# SparkFun_Main_Board_Double_v20.net
KiCad netlist of a schematic drawn in EAGLE
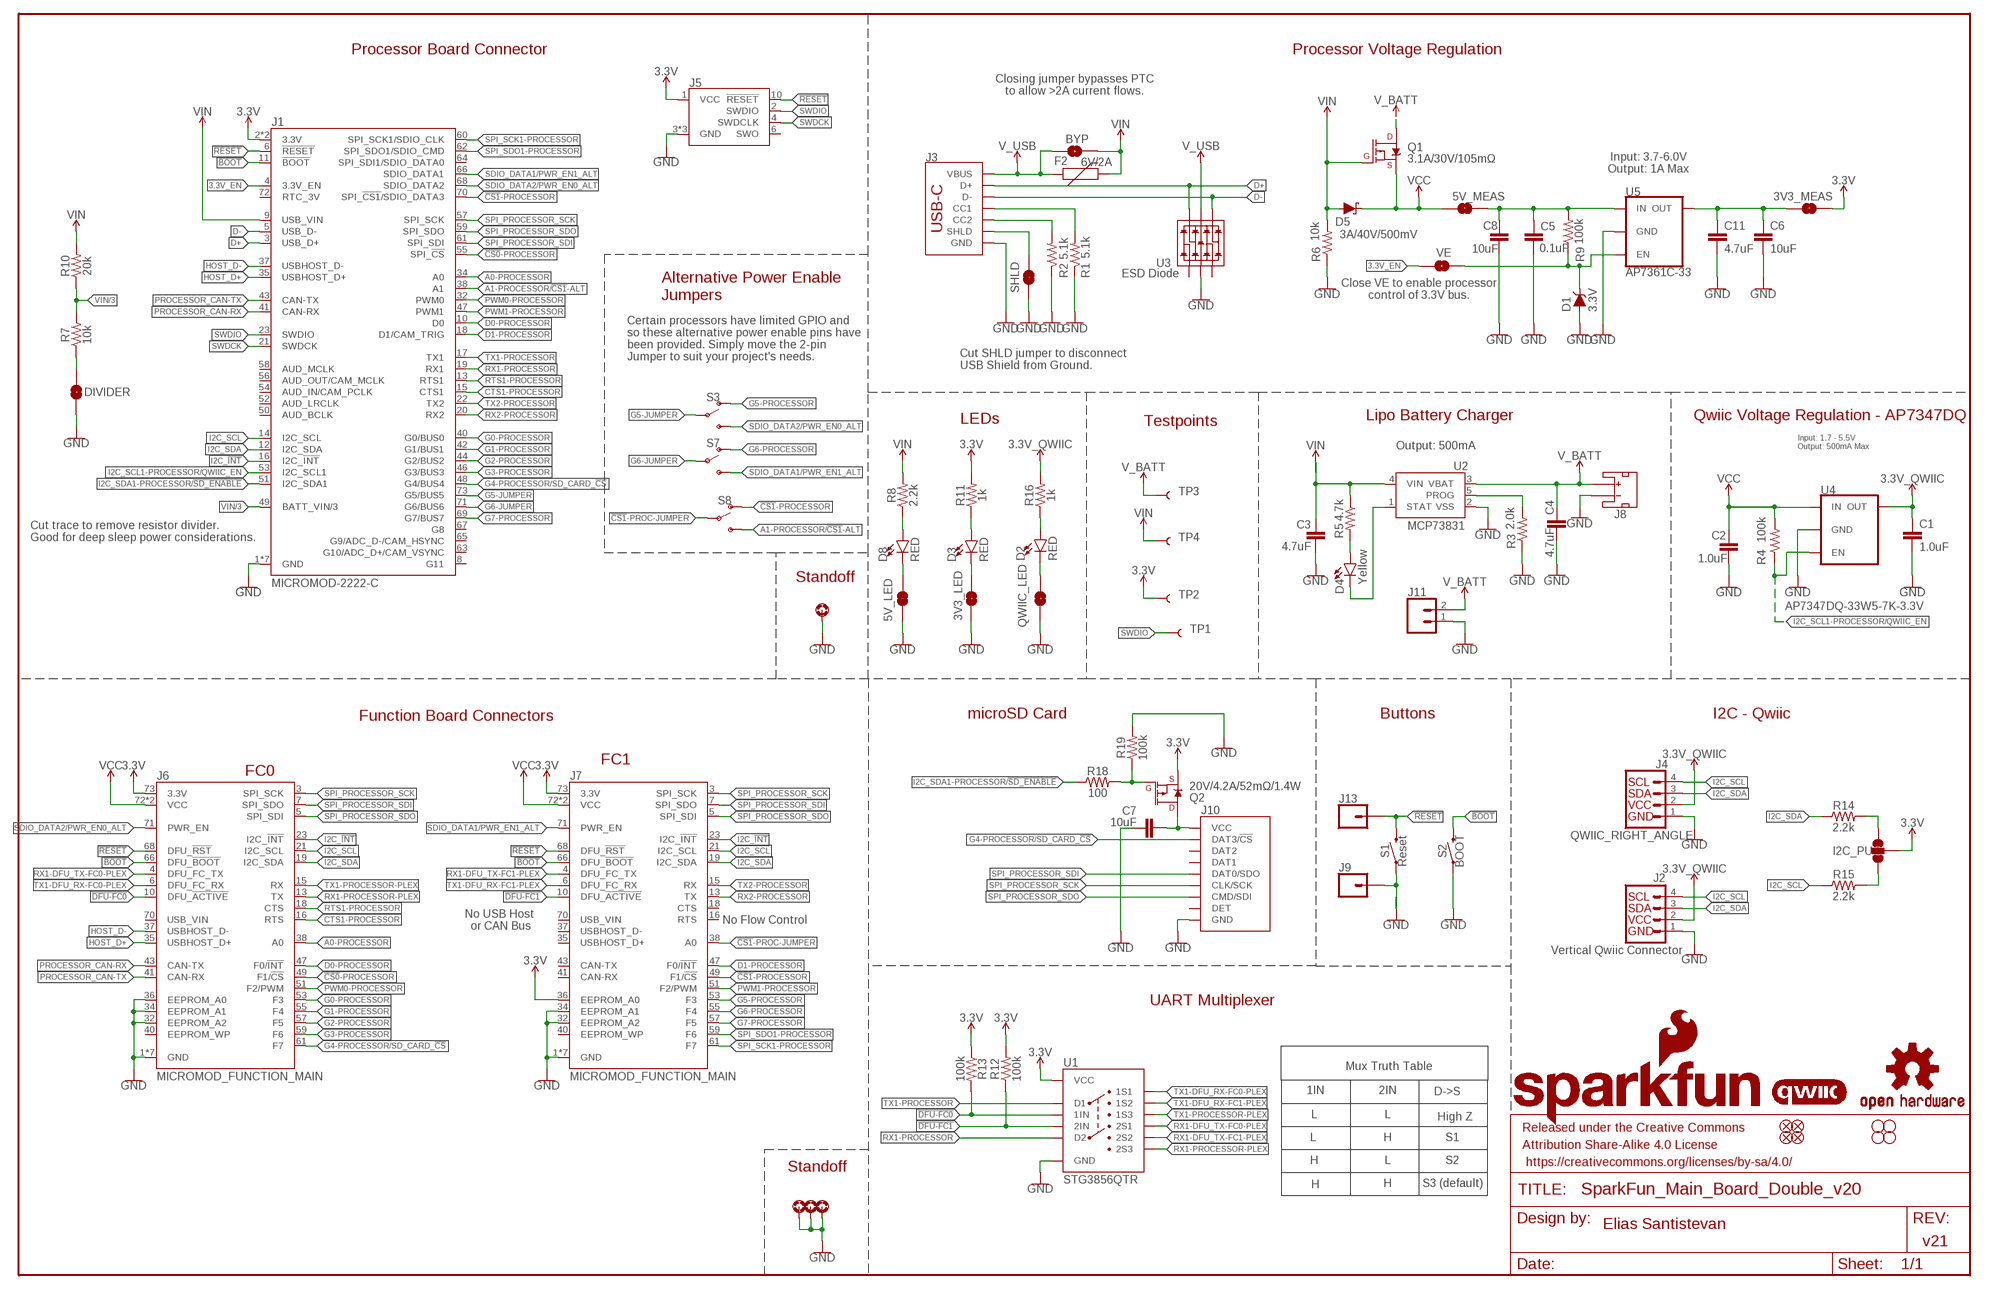
[diagram p0: schematic, sheet 1]

(export (version "E")
  (design (tool "Eeschema 10.0.6"))
  (components
    (comp (ref "3V3_LED")
      (value "JUMPER-SMT_2_NC_TRACE_SILK")
      (footprint "eagle-import:SMT-JUMPER_2_NC_TRACE_SILK")
      (libsource (lib "eagle-import") (part "JUMPER-SMT_2_NC_TRACE_SILK"))
    )
    (comp (ref "3V3_MEAS")
      (value "JUMPER-COMBO_2_NC_TRACE")
      (footprint "eagle-import:COMBO-JUMPER_2_NC_TRACE")
      (libsource (lib "eagle-import") (part "JUMPER-COMBO_2_NC_TRACE"))
    )
    (comp (ref "5V_LED")
      (value "JUMPER-SMT_2_NC_TRACE_SILK")
      (footprint "eagle-import:SMT-JUMPER_2_NC_TRACE_SILK")
      (libsource (lib "eagle-import") (part "JUMPER-SMT_2_NC_TRACE_SILK"))
    )
    (comp (ref "5V_MEAS")
      (value "JUMPER-COMBO_2_NC_TRACE")
      (footprint "eagle-import:COMBO-JUMPER_2_NC_TRACE")
      (libsource (lib "eagle-import") (part "JUMPER-COMBO_2_NC_TRACE"))
    )
    (comp (ref "BYP")
      (value "JUMPER-SMT_2_NO_SILK")
      (footprint "eagle-import:SMT-JUMPER_2_NO_SILK")
      (libsource (lib "eagle-import") (part "JUMPER-SMT_2_NO_SILK"))
    )
    (comp (ref "C1")
      (value "1.0uF")
      (footprint "eagle-import:0603")
      (libsource (lib "eagle-import") (part "1.0UF-0603-16V-10%"))
    )
    (comp (ref "C2")
      (value "1.0uF")
      (footprint "eagle-import:0603")
      (libsource (lib "eagle-import") (part "1.0UF-0603-16V-10%"))
    )
    (comp (ref "C3")
      (value "4.7uF")
      (footprint "eagle-import:0603")
      (libsource (lib "eagle-import") (part "4.7UF-0603-6.3V-(10%)"))
    )
    (comp (ref "C4")
      (value "4.7uF")
      (footprint "eagle-import:0603")
      (libsource (lib "eagle-import") (part "4.7UF-0603-35V-(20%)"))
    )
    (comp (ref "C5")
      (value "0.1uF")
      (footprint "eagle-import:0603")
      (libsource (lib "eagle-import") (part "0.1UF-0603-25V-(+80/-20%)"))
    )
    (comp (ref "C6")
      (value "10uF")
      (footprint "eagle-import:0805")
      (libsource (lib "eagle-import") (part "10UF-0805-10V-10%"))
    )
    (comp (ref "C7")
      (value "10uF")
      (footprint "eagle-import:0603")
      (libsource (lib "eagle-import") (part "10UF-0603-6.3V-20%"))
    )
    (comp (ref "C8")
      (value "10uF")
      (footprint "eagle-import:0805")
      (libsource (lib "eagle-import") (part "10UF-0805-10V-10%"))
    )
    (comp (ref "C11")
      (value "4.7uF")
      (footprint "eagle-import:0603")
      (libsource (lib "eagle-import") (part "4.7UF-0603-6.3V-(10%)"))
    )
    (comp (ref "D1")
      (value "3.3V")
      (footprint "eagle-import:SOD-323")
      (libsource (lib "eagle-import") (part "DIODE-ZENER-MM3Z3V3T1G"))
    )
    (comp (ref "D2")
      (value "RED")
      (footprint "eagle-import:LED-0603")
      (libsource (lib "eagle-import") (part "LED-RED0603"))
    )
    (comp (ref "D3")
      (value "RED")
      (footprint "eagle-import:LED-0603")
      (libsource (lib "eagle-import") (part "LED-RED0603"))
    )
    (comp (ref "D4")
      (value "Yellow")
      (footprint "eagle-import:LED-0603")
      (libsource (lib "eagle-import") (part "LED-YELLOW0603"))
    )
    (comp (ref "D5")
      (value "3A/40V/500mV")
      (footprint "eagle-import:SMA-DIODE")
      (libsource (lib "eagle-import") (part "DIODE-SCHOTTKY-B340A"))
    )
    (comp (ref "D8")
      (value "RED")
      (footprint "eagle-import:LED-0603")
      (libsource (lib "eagle-import") (part "LED-RED0603"))
    )
    (comp (ref "DIVIDER")
      (value "JUMPER-SMT_2_NC_TRACE_SILK")
      (footprint "eagle-import:SMT-JUMPER_2_NC_TRACE_SILK")
      (libsource (lib "eagle-import") (part "JUMPER-SMT_2_NC_TRACE_SILK"))
    )
    (comp (ref "F2")
      (value "6V/2A")
      (footprint "eagle-import:1210")
      (libsource (lib "eagle-import") (part "PPTC_6V2A"))
    )
    (comp (ref "FD1")
      (value "FIDUCIAL1X2")
      (footprint "eagle-import:FIDUCIAL-1X2")
      (libsource (lib "eagle-import") (part "FIDUCIAL1X2"))
    )
    (comp (ref "FD2")
      (value "FIDUCIAL1X2")
      (footprint "eagle-import:FIDUCIAL-1X2")
      (libsource (lib "eagle-import") (part "FIDUCIAL1X2"))
    )
    (comp (ref "FD3")
      (value "FIDUCIAL1X2")
      (footprint "eagle-import:FIDUCIAL-1X2")
      (libsource (lib "eagle-import") (part "FIDUCIAL1X2"))
    )
    (comp (ref "FD4")
      (value "FIDUCIAL1X2")
      (footprint "eagle-import:FIDUCIAL-1X2")
      (libsource (lib "eagle-import") (part "FIDUCIAL1X2"))
    )
    (comp (ref "FRAME1")
      (value "FRAME-LEDGER")
      (footprint "eagle-import:CREATIVE_COMMONS")
      (libsource (lib "eagle-import") (part "FRAME-LEDGER"))
    )
    (comp (ref "H2")
      (value "STAND-OFF-REFLOW-M2.5_2.5MM_TALL")
      (footprint "eagle-import:STAND-OFF-REFLOW-M2.5")
      (libsource (lib "eagle-import") (part "STAND-OFF-REFLOW-M2.5_2.5MM_TALL"))
    )
    (comp (ref "H3")
      (value "STAND-OFF-REFLOW-M2.5_2.5MM_TALL")
      (footprint "eagle-import:STAND-OFF-REFLOW-M2.5")
      (libsource (lib "eagle-import") (part "STAND-OFF-REFLOW-M2.5_2.5MM_TALL"))
    )
    (comp (ref "H4")
      (value "STAND-OFF-REFLOW-M2.5_2.5MM_TALL")
      (footprint "eagle-import:STAND-OFF-REFLOW-M2.5")
      (libsource (lib "eagle-import") (part "STAND-OFF-REFLOW-M2.5_2.5MM_TALL"))
    )
    (comp (ref "H8")
      (value "STAND-OFF-REFLOW-M2.5_2.5MM_TALL")
      (footprint "eagle-import:STAND-OFF-REFLOW-M2.5")
      (libsource (lib "eagle-import") (part "STAND-OFF-REFLOW-M2.5_2.5MM_TALL"))
    )
    (comp (ref "H14")
      (value "STAND-OFFTIGHT")
      (footprint "eagle-import:STAND-OFF-TIGHT")
      (libsource (lib "eagle-import") (part "STAND-OFFTIGHT"))
    )
    (comp (ref "H15")
      (value "STAND-OFFTIGHT")
      (footprint "eagle-import:STAND-OFF-TIGHT")
      (libsource (lib "eagle-import") (part "STAND-OFFTIGHT"))
    )
    (comp (ref "H16")
      (value "STAND-OFFTIGHT")
      (footprint "eagle-import:STAND-OFF-TIGHT")
      (libsource (lib "eagle-import") (part "STAND-OFFTIGHT"))
    )
    (comp (ref "H17")
      (value "STAND-OFFTIGHT")
      (footprint "eagle-import:STAND-OFF-TIGHT")
      (libsource (lib "eagle-import") (part "STAND-OFFTIGHT"))
    )
    (comp (ref "I2C_PU")
      (value "JUMPER-SMT_3_2-NC_TRACE_SILK")
      (footprint "eagle-import:SMT-JUMPER_3_2-NC_TRACE_SILK")
      (libsource (lib "eagle-import") (part "JUMPER-SMT_3_2-NC_TRACE_SILK"))
    )
    (comp (ref "J1")
      (value "MICROMOD-2222-C")
      (footprint "eagle-import:M.2-CONNECTOR-E")
      (libsource (lib "eagle-import") (part "MICROMOD-2222-C"))
    )
    (comp (ref "J2")
      (value "Vertical Qwiic Connector")
      (footprint "eagle-import:JST04_1MM_VERT")
      (libsource (lib "eagle-import") (part "QWIIC_CONNECTOR"))
    )
    (comp (ref "J3")
      (value "USB_C_2-LAYER_PADS")
      (footprint "eagle-import:USB-C-16P-2LAYER-PADS")
      (libsource (lib "eagle-import") (part "USB_C_2-LAYER_PADS"))
    )
    (comp (ref "J4")
      (value "QWIIC_RIGHT_ANGLE")
      (footprint "eagle-import:JST04_1MM_RA")
      (libsource (lib "eagle-import") (part "QWIIC_CONNECTORJS-1MM"))
    )
    (comp (ref "J5")
      (value "CORTEX_JTAG_DEBUG_MINIMUM_PTH")
      (footprint "eagle-import:2X5-PTH-1.27MM")
      (libsource (lib "eagle-import") (part "CORTEX_JTAG_DEBUG_MINIMUM_PTH"))
    )
    (comp (ref "J6")
      (value "MICROMOD_FUNCTION_MAIN")
      (footprint "eagle-import:M.2-CONNECTOR-E-FUNCTION-STANDARD")
      (libsource (lib "eagle-import") (part "MICROMOD_FUNCTION_MAIN"))
    )
    (comp (ref "J7")
      (value "MICROMOD_FUNCTION_MAIN")
      (footprint "eagle-import:M.2-CONNECTOR-E-FUNCTION-STANDARD")
      (libsource (lib "eagle-import") (part "MICROMOD_FUNCTION_MAIN"))
    )
    (comp (ref "J8")
      (value "JST_2MM_MALE")
      (footprint "eagle-import:JST-2-SMD")
      (libsource (lib "eagle-import") (part "JST_2MM_MALE"))
    )
    (comp (ref "J9")
      (value "CONN_01PTH_NO_SILK_YES_STOP")
      (footprint "eagle-import:1X01_NO_SILK")
      (libsource (lib "eagle-import") (part "CONN_01PTH_NO_SILK_YES_STOP"))
    )
    (comp (ref "J10")
      (value "MICRO-SD-PUSH-PUSH-EXT-PIN")
      (footprint "eagle-import:MICROSD-EXTERNALPIN")
      (libsource (lib "eagle-import") (part "MICRO-SD-PUSH-PUSH-EXT-PIN"))
    )
    (comp (ref "J11")
      (value "CONN_021X02_NO_SILK")
      (footprint "eagle-import:1X02_NO_SILK")
      (libsource (lib "eagle-import") (part "CONN_021X02_NO_SILK"))
    )
    (comp (ref "J13")
      (value "CONN_01PTH_NO_SILK_YES_STOP")
      (footprint "eagle-import:1X01_NO_SILK")
      (libsource (lib "eagle-import") (part "CONN_01PTH_NO_SILK_YES_STOP"))
    )
    (comp (ref "LOGO1")
      (value "QWIIC_LOGO_8MM")
      (footprint "eagle-import:QWIIC_8MM")
      (libsource (lib "eagle-import") (part "QWIIC_LOGO_8MM"))
    )
    (comp (ref "LOGO2")
      (value "SFE_LOGO_NAME_FLAME.3_INCH")
      (footprint "eagle-import:SFE_LOGO_NAME_FLAME_.3")
      (libsource (lib "eagle-import") (part "SFE_LOGO_NAME_FLAME.3_INCH"))
    )
    (comp (ref "LOGO3")
      (value "OSHW-LOGOL")
      (footprint "eagle-import:OSHW-LOGO-L")
      (libsource (lib "eagle-import") (part "OSHW-LOGOL"))
    )
    (comp (ref "Q1")
      (value "3.1A/30V/105mΩ")
      (footprint "eagle-import:SOT23-3")
      (libsource (lib "eagle-import") (part "MOSFET_PCH-DMG2307L"))
    )
    (comp (ref "Q2")
      (value "20V/4.2A/52mΩ/1.4W")
      (footprint "eagle-import:SOT23-3")
      (libsource (lib "eagle-import") (part "MOSFET_PCH-DMG2305UX-7"))
    )
    (comp (ref "QWIIC_LED")
      (value "JUMPER-SMT_2_NC_TRACE_SILK")
      (footprint "eagle-import:SMT-JUMPER_2_NC_TRACE_SILK")
      (libsource (lib "eagle-import") (part "JUMPER-SMT_2_NC_TRACE_SILK"))
    )
    (comp (ref "R1")
      (value "5.1k")
      (footprint "eagle-import:0603")
      (libsource (lib "eagle-import") (part "5.1KOHM5.1KOHM-0603-1/10W-1%"))
    )
    (comp (ref "R2")
      (value "5.1k")
      (footprint "eagle-import:0603")
      (libsource (lib "eagle-import") (part "5.1KOHM5.1KOHM-0603-1/10W-1%"))
    )
    (comp (ref "R3")
      (value "2.0k")
      (footprint "eagle-import:0603")
      (libsource (lib "eagle-import") (part "2.0KOHM-0603-1/10W-5%"))
    )
    (comp (ref "R4")
      (value "100k")
      (footprint "eagle-import:0603")
      (libsource (lib "eagle-import") (part "100KOHM-0603-1/10W-1%"))
    )
    (comp (ref "R5")
      (value "4.7k")
      (footprint "eagle-import:0603")
      (libsource (lib "eagle-import") (part "4.7KOHM-0603-1/10W-1%"))
    )
    (comp (ref "R6")
      (value "10k")
      (footprint "eagle-import:0603")
      (libsource (lib "eagle-import") (part "10KOHM-0603-1/10W-1%"))
    )
    (comp (ref "R7")
      (value "10k")
      (footprint "eagle-import:0603")
      (libsource (lib "eagle-import") (part "10KOHM-0603-1/10W-1%"))
    )
    (comp (ref "R8")
      (value "2.2k")
      (footprint "eagle-import:0603")
      (libsource (lib "eagle-import") (part "2.2KOHM-0603-1/10W-1%"))
    )
    (comp (ref "R9")
      (value "100k")
      (footprint "eagle-import:0603")
      (libsource (lib "eagle-import") (part "100KOHM-0603-1/10W-1%"))
    )
    (comp (ref "R10")
      (value "20k")
      (footprint "eagle-import:0603")
      (libsource (lib "eagle-import") (part "20KOHM-0603-1/10W-1%"))
    )
    (comp (ref "R11")
      (value "1k")
      (footprint "eagle-import:0603")
      (libsource (lib "eagle-import") (part "1KOHM-0603-1/10W-1%"))
    )
    (comp (ref "R12")
      (value "100k")
      (footprint "eagle-import:0603")
      (libsource (lib "eagle-import") (part "100KOHM-0603-1/10W-1%"))
    )
    (comp (ref "R13")
      (value "100k")
      (footprint "eagle-import:0603")
      (libsource (lib "eagle-import") (part "100KOHM-0603-1/10W-1%"))
    )
    (comp (ref "R14")
      (value "2.2k")
      (footprint "eagle-import:0603")
      (libsource (lib "eagle-import") (part "2.2KOHM-0603-1/10W-1%"))
    )
    (comp (ref "R15")
      (value "2.2k")
      (footprint "eagle-import:0603")
      (libsource (lib "eagle-import") (part "2.2KOHM-0603-1/10W-1%"))
    )
    (comp (ref "R16")
      (value "1k")
      (footprint "eagle-import:0603")
      (libsource (lib "eagle-import") (part "1KOHM-0603-1/10W-1%"))
    )
    (comp (ref "R18")
      (value "100")
      (footprint "eagle-import:0603")
      (libsource (lib "eagle-import") (part "100OHM-0603-1/10W-1%"))
    )
    (comp (ref "R19")
      (value "100k")
      (footprint "eagle-import:0603")
      (libsource (lib "eagle-import") (part "100KOHM-0603-1/10W-1%"))
    )
    (comp (ref "S1")
      (value "Reset")
      (footprint "eagle-import:TACTILE_SWITCH_SMD_5.2MM")
      (libsource (lib "eagle-import") (part "MOMENTARY-SWITCH-SPST-SMD-5.2-TALL-REDUNDANT"))
    )
    (comp (ref "S2")
      (value "BOOT")
      (footprint "eagle-import:TACTILE_SWITCH_SMD_5.2MM")
      (libsource (lib "eagle-import") (part "MOMENTARY-SWITCH-SPST-SMD-5.2-TALL-REDUNDANT"))
    )
    (comp (ref "S3")
      (value "SWITCH-SPDT-SMD-RIGHT-ANGLE")
      (footprint "eagle-import:SWITCH_SPST_SMD_A")
      (libsource (lib "eagle-import") (part "SWITCH-SPDT-SMD-RIGHT-ANGLE"))
    )
    (comp (ref "S7")
      (value "SWITCH-SPDT-SMD-RIGHT-ANGLE")
      (footprint "eagle-import:SWITCH_SPST_SMD_A")
      (libsource (lib "eagle-import") (part "SWITCH-SPDT-SMD-RIGHT-ANGLE"))
    )
    (comp (ref "S8")
      (value "SWITCH-SPDT-SMD-RIGHT-ANGLE")
      (footprint "eagle-import:SWITCH_SPST_SMD_A")
      (libsource (lib "eagle-import") (part "SWITCH-SPDT-SMD-RIGHT-ANGLE"))
    )
    (comp (ref "SHLD")
      (value "JUMPER-SMT_2_NC_TRACE_SILK")
      (footprint "eagle-import:SMT-JUMPER_2_NC_TRACE_SILK")
      (libsource (lib "eagle-import") (part "JUMPER-SMT_2_NC_TRACE_SILK"))
    )
    (comp (ref "TP1")
      (value "TEST-POINT3X5")
      (footprint "eagle-import:PAD.03X.05")
      (libsource (lib "eagle-import") (part "TEST-POINT3X5"))
    )
    (comp (ref "TP2")
      (value "TEST-POINT3X5")
      (footprint "eagle-import:PAD.03X.05")
      (libsource (lib "eagle-import") (part "TEST-POINT3X5"))
    )
    (comp (ref "TP3")
      (value "TEST-POINT3X5")
      (footprint "eagle-import:PAD.03X.05")
      (libsource (lib "eagle-import") (part "TEST-POINT3X5"))
    )
    (comp (ref "TP4")
      (value "TEST-POINT3X5")
      (footprint "eagle-import:PAD.03X.05")
      (libsource (lib "eagle-import") (part "TEST-POINT3X5"))
    )
    (comp (ref "U1")
      (value "STG3856QTR")
      (footprint "eagle-import:STG3856")
      (libsource (lib "eagle-import") (part "STG3856QTR"))
    )
    (comp (ref "U2")
      (value "MCP73831")
      (footprint "eagle-import:SOT23-5")
      (libsource (lib "eagle-import") (part "MCP73831"))
    )
    (comp (ref "U3")
      (value "ESD Diode")
      (footprint "eagle-import:SOT-23-6")
      (libsource (lib "eagle-import") (part "TVS_DIODE_ARRAYSMD"))
    )
    (comp (ref "U4")
      (value "AP7347DQ-33W5-7K-3.3V")
      (footprint "eagle-import:SOT25")
      (libsource (lib "eagle-import") (part "AP7347DQ-33W5-7K-3.3V"))
    )
    (comp (ref "U5")
      (value "AP7361C-33")
      (footprint "eagle-import:UDFN-8")
      (libsource (lib "eagle-import") (part "AP7361C-33FGEUDFN-8"))
    )
    (comp (ref "VE")
      (value "JUMPER-SMT_2_NO_SILK")
      (footprint "eagle-import:SMT-JUMPER_2_NO_SILK")
      (libsource (lib "eagle-import") (part "JUMPER-SMT_2_NO_SILK"))
    )
  )
  (nets
    (net (code "1") (name "/A1-PROCESSOR{slash}~{CS1}-ALT") (class "Default")
      (node (ref "J1") (pin "38") (pinfunction "A1_38") (pintype "bidirectional"))
      (node (ref "S8") (pin "3") (pinfunction "S_3") (pintype "passive"))
    )
    (net (code "2") (name "/G4-PROCESSOR{slash}SD_CARD_~{CS}") (class "Default")
      (node (ref "J1") (pin "48") (pinfunction "G4/BUS4_48") (pintype "bidirectional"))
      (node (ref "J10") (pin "2") (pinfunction "DAT3/~{CS}_2") (pintype "bidirectional"))
      (node (ref "J6") (pin "61") (pinfunction "F7_61") (pintype "bidirectional"))
    )
    (net (code "3") (name "/I2C_SDA1-PROCESSOR{slash}~{SD_ENABLE}") (class "Default")
      (node (ref "J1") (pin "51") (pinfunction "I2C_SDA1_51") (pintype "bidirectional"))
      (node (ref "R18") (pin "1") (pinfunction "1_1") (pintype "passive"))
    )
    (net (code "4") (name "/I2C_~{INT}") (class "Default")
      (node (ref "J1") (pin "16") (pinfunction "I2C_~{INT}_16") (pintype "bidirectional"))
      (node (ref "J6") (pin "23") (pinfunction "I2C_~{INT}_23") (pintype "bidirectional"))
      (node (ref "J7") (pin "23") (pinfunction "I2C_~{INT}_23") (pintype "bidirectional"))
    )
    (net (code "5") (name "/~{BOOT}") (class "Default")
      (node (ref "J1") (pin "11") (pinfunction "~{BOOT}_11") (pintype "bidirectional"))
      (node (ref "J6") (pin "66") (pinfunction "DFU_~{BOOT}_66") (pintype "bidirectional"))
      (node (ref "J7") (pin "66") (pinfunction "DFU_~{BOOT}_66") (pintype "bidirectional"))
      (node (ref "S2") (pin "3") (pinfunction "2_3") (pintype "passive"))
      (node (ref "S2") (pin "4") (pinfunction "2_4") (pintype "passive"))
    )
    (net (code "6") (name "/~{CS0}-PROCESSOR") (class "Default")
      (node (ref "J1") (pin "55") (pinfunction "SPI_~{CS}_55") (pintype "bidirectional"))
      (node (ref "J6") (pin "49") (pinfunction "F1/~{CS}_49") (pintype "bidirectional"))
    )
    (net (code "7") (name "/~{CS1}-PROC-JUMPER") (class "Default")
      (node (ref "J7") (pin "38") (pinfunction "A0_38") (pintype "bidirectional"))
      (node (ref "S8") (pin "2") (pinfunction "P_2") (pintype "passive"))
    )
    (net (code "8") (name "/~{CS1}-PROCESSOR") (class "Default")
      (node (ref "J1") (pin "70") (pinfunction "SPI_~{CS1}/SDIO_DATA3_70") (pintype "bidirectional"))
      (node (ref "J7") (pin "49") (pinfunction "F1/~{CS}_49") (pintype "bidirectional"))
      (node (ref "S8") (pin "1") (pinfunction "O_1") (pintype "passive"))
    )
    (net (code "9") (name "/~{DFU-FC0}") (class "Default")
      (node (ref "J6") (pin "10") (pinfunction "DFU_~{ACTIVE}_10") (pintype "bidirectional"))
      (node (ref "R13") (pin "2") (pinfunction "2_2") (pintype "passive"))
      (node (ref "U1") (pin "P12") (pinfunction "1IN_P12") (pintype "bidirectional"))
    )
    (net (code "10") (name "/~{DFU-FC1}") (class "Default")
      (node (ref "J7") (pin "10") (pinfunction "DFU_~{ACTIVE}_10") (pintype "bidirectional"))
      (node (ref "R12") (pin "1") (pinfunction "1_1") (pintype "passive"))
      (node (ref "U1") (pin "P10") (pinfunction "2IN_P10") (pintype "bidirectional"))
    )
    (net (code "11") (name "/~{RESET}") (class "Default")
      (node (ref "J1") (pin "6") (pinfunction "~{RESET}_6") (pintype "bidirectional"))
      (node (ref "J13") (pin "1") (pinfunction "1_1") (pintype "passive"))
      (node (ref "J5") (pin "10") (pinfunction "~{RESET}_10") (pintype "bidirectional"))
      (node (ref "J6") (pin "68") (pinfunction "DFU_~{RST}_68") (pintype "bidirectional"))
      (node (ref "J7") (pin "68") (pinfunction "DFU_~{RST}_68") (pintype "bidirectional"))
      (node (ref "S1") (pin "3") (pinfunction "2_3") (pintype "passive"))
      (node (ref "S1") (pin "4") (pinfunction "2_4") (pintype "passive"))
    )
    (net (code "12") (name "3.3V") (class "Default")
      (node (ref "3V3_MEAS") (pin "2") (pinfunction "2_2") (pintype "passive"))
      (node (ref "3V3_MEAS") (pin "4") (pinfunction "2_4") (pintype "passive"))
      (node (ref "I2C_PU") (pin "2") (pinfunction "2_2") (pintype "passive"))
      (node (ref "J1") (pin "2") (pinfunction "3.3V_2") (pintype "bidirectional"))
      (node (ref "J1") (pin "74") (pinfunction "3.3V_74") (pintype "bidirectional"))
      (node (ref "J5") (pin "1") (pinfunction "VCC_1") (pintype "bidirectional"))
      (node (ref "J6") (pin "73") (pinfunction "3.3V_73") (pintype "bidirectional"))
      (node (ref "J7") (pin "36") (pinfunction "EEPROM_A0_36") (pintype "bidirectional"))
      (node (ref "J7") (pin "73") (pinfunction "3.3V_73") (pintype "bidirectional"))
      (node (ref "Q2") (pin "2") (pinfunction "S_2") (pintype "bidirectional"))
      (node (ref "R11") (pin "2") (pinfunction "2_2") (pintype "passive"))
      (node (ref "R12") (pin "2") (pinfunction "2_2") (pintype "passive"))
      (node (ref "R13") (pin "1") (pinfunction "1_1") (pintype "passive"))
      (node (ref "TP2") (pin "1") (pinfunction "1_1") (pintype "bidirectional"))
      (node (ref "U1") (pin "P11") (pinfunction "VCC_P11") (pintype "power_in"))
    )
    (net (code "13") (name "3.3V_EN") (class "Default")
      (node (ref "J1") (pin "4") (pinfunction "3.3V_EN_4") (pintype "bidirectional"))
      (node (ref "VE") (pin "1") (pinfunction "1_1") (pintype "passive"))
    )
    (net (code "14") (name "3.3V_QWIIC") (class "Default")
      (node (ref "C1") (pin "1") (pinfunction "1_1") (pintype "passive"))
      (node (ref "J2") (pin "2") (pinfunction "2_2") (pintype "power_in"))
      (node (ref "J4") (pin "2") (pinfunction "2_2") (pintype "power_in"))
      (node (ref "R16") (pin "2") (pinfunction "2_2") (pintype "passive"))
      (node (ref "U4") (pin "5") (pinfunction "OUT_5") (pintype "passive"))
    )
    (net (code "15") (name "A0-PROCESSOR") (class "Default")
      (node (ref "J1") (pin "34") (pinfunction "A0_34") (pintype "bidirectional"))
      (node (ref "J6") (pin "38") (pinfunction "A0_38") (pintype "bidirectional"))
    )
    (net (code "16") (name "CTS1-PROCESSOR") (class "Default")
      (node (ref "J1") (pin "15") (pinfunction "CTS1_15") (pintype "bidirectional"))
      (node (ref "J6") (pin "16") (pinfunction "RTS_16") (pintype "bidirectional"))
    )
    (net (code "17") (name "D+") (class "Default")
      (node (ref "J1") (pin "3") (pinfunction "USB_D+_3") (pintype "bidirectional"))
      (node (ref "J3") (pin "A6") (pinfunction "D+_A6") (pintype "bidirectional"))
      (node (ref "J3") (pin "B6") (pinfunction "D+_B6") (pintype "bidirectional"))
      (node (ref "U3") (pin "6") (pinfunction "IO4_6") (pintype "bidirectional"))
    )
    (net (code "18") (name "D-") (class "Default")
      (node (ref "J1") (pin "5") (pinfunction "USB_D-_5") (pintype "bidirectional"))
      (node (ref "J3") (pin "A7") (pinfunction "D-_A7") (pintype "bidirectional"))
      (node (ref "J3") (pin "B7") (pinfunction "D-_B7") (pintype "bidirectional"))
      (node (ref "U3") (pin "4") (pinfunction "IO3_4") (pintype "bidirectional"))
    )
    (net (code "19") (name "D0-PROCESSOR") (class "Default")
      (node (ref "J1") (pin "10") (pinfunction "D0_10") (pintype "bidirectional"))
      (node (ref "J6") (pin "47") (pinfunction "F0/~{INT}_47") (pintype "bidirectional"))
    )
    (net (code "20") (name "D1-PROCESSOR") (class "Default")
      (node (ref "J1") (pin "18") (pinfunction "D1/CAM_TRIG_18") (pintype "bidirectional"))
      (node (ref "J7") (pin "47") (pinfunction "F0/~{INT}_47") (pintype "bidirectional"))
    )
    (net (code "21") (name "G0-PROCESSOR") (class "Default")
      (node (ref "J1") (pin "40") (pinfunction "G0/BUS0_40") (pintype "bidirectional"))
      (node (ref "J6") (pin "53") (pinfunction "F3_53") (pintype "bidirectional"))
    )
    (net (code "22") (name "G1-PROCESSOR") (class "Default")
      (node (ref "J1") (pin "42") (pinfunction "G1/BUS1_42") (pintype "bidirectional"))
      (node (ref "J6") (pin "55") (pinfunction "F4_55") (pintype "bidirectional"))
    )
    (net (code "23") (name "G2-PROCESSOR") (class "Default")
      (node (ref "J1") (pin "44") (pinfunction "G2/BUS2_44") (pintype "bidirectional"))
      (node (ref "J6") (pin "57") (pinfunction "F5_57") (pintype "bidirectional"))
    )
    (net (code "24") (name "G3-PROCESSOR") (class "Default")
      (node (ref "J1") (pin "46") (pinfunction "G3/BUS3_46") (pintype "bidirectional"))
      (node (ref "J6") (pin "59") (pinfunction "F6_59") (pintype "bidirectional"))
    )
    (net (code "25") (name "G5-JUMPER") (class "Default")
      (node (ref "J1") (pin "73") (pinfunction "G5/BUS5_73") (pintype "bidirectional"))
      (node (ref "S3") (pin "2") (pinfunction "P_2") (pintype "passive"))
    )
    (net (code "26") (name "G5-PROCESSOR") (class "Default")
      (node (ref "J7") (pin "53") (pinfunction "F3_53") (pintype "bidirectional"))
      (node (ref "S3") (pin "1") (pinfunction "O_1") (pintype "passive"))
    )
    (net (code "27") (name "G6-JUMPER") (class "Default")
      (node (ref "J1") (pin "71") (pinfunction "G6/BUS6_71") (pintype "bidirectional"))
      (node (ref "S7") (pin "2") (pinfunction "P_2") (pintype "passive"))
    )
    (net (code "28") (name "G6-PROCESSOR") (class "Default")
      (node (ref "J7") (pin "55") (pinfunction "F4_55") (pintype "bidirectional"))
      (node (ref "S7") (pin "1") (pinfunction "O_1") (pintype "passive"))
    )
    (net (code "29") (name "G7-PROCESSOR") (class "Default")
      (node (ref "J1") (pin "69") (pinfunction "G7/BUS7_69") (pintype "bidirectional"))
      (node (ref "J7") (pin "57") (pinfunction "F5_57") (pintype "bidirectional"))
    )
    (net (code "30") (name "GND") (class "Default")
      (node (ref "3V3_LED") (pin "1") (pinfunction "1_1") (pintype "passive"))
      (node (ref "5V_LED") (pin "1") (pinfunction "1_1") (pintype "passive"))
      (node (ref "C1") (pin "2") (pinfunction "2_2") (pintype "passive"))
      (node (ref "C11") (pin "2") (pinfunction "2_2") (pintype "passive"))
      (node (ref "C2") (pin "2") (pinfunction "2_2") (pintype "passive"))
      (node (ref "C3") (pin "2") (pinfunction "2_2") (pintype "passive"))
      (node (ref "C4") (pin "2") (pinfunction "2_2") (pintype "passive"))
      (node (ref "C5") (pin "2") (pinfunction "2_2") (pintype "passive"))
      (node (ref "C6") (pin "2") (pinfunction "2_2") (pintype "passive"))
      (node (ref "C7") (pin "1") (pinfunction "1_1") (pintype "passive"))
      (node (ref "C8") (pin "2") (pinfunction "2_2") (pintype "passive"))
      (node (ref "D1") (pin "A") (pinfunction "A_A") (pintype "passive"))
      (node (ref "DIVIDER") (pin "1") (pinfunction "1_1") (pintype "passive"))
      (node (ref "H2") (pin "1") (pinfunction "1_1") (pintype "bidirectional"))
      (node (ref "H3") (pin "1") (pinfunction "1_1") (pintype "bidirectional"))
      (node (ref "H4") (pin "1") (pinfunction "1_1") (pintype "bidirectional"))
      (node (ref "H8") (pin "1") (pinfunction "1_1") (pintype "bidirectional"))
      (node (ref "J1") (pin "1") (pinfunction "GND_1") (pintype "bidirectional"))
      (node (ref "J1") (pin "33") (pinfunction "GND_33") (pintype "bidirectional"))
      (node (ref "J1") (pin "36") (pinfunction "GND_36") (pintype "bidirectional"))
      (node (ref "J1") (pin "39") (pinfunction "GND_39") (pintype "bidirectional"))
      (node (ref "J1") (pin "45") (pinfunction "GND_45") (pintype "bidirectional"))
      (node (ref "J1") (pin "7") (pinfunction "GND_7") (pintype "bidirectional"))
      (node (ref "J1") (pin "75") (pinfunction "GND_75") (pintype "bidirectional"))
      (node (ref "J10") (pin "10") (pinfunction "GND_10") (pintype "bidirectional"))
      (node (ref "J10") (pin "11") (pinfunction "GND_11") (pintype "bidirectional"))
      (node (ref "J10") (pin "12") (pinfunction "GND_12") (pintype "bidirectional"))
      (node (ref "J10") (pin "13") (pinfunction "GND_13") (pintype "bidirectional"))
      (node (ref "J10") (pin "6") (pinfunction "GND_6") (pintype "bidirectional"))
      (node (ref "J11") (pin "1") (pinfunction "1_1") (pintype "passive"))
      (node (ref "J2") (pin "1") (pinfunction "1_1") (pintype "power_in"))
      (node (ref "J3") (pin "GND") (pinfunction "GND_GND") (pintype "bidirectional"))
      (node (ref "J3") (pin "GND2") (pinfunction "GND_GND2") (pintype "bidirectional"))
      (node (ref "J4") (pin "1") (pinfunction "1_1") (pintype "power_in"))
      (node (ref "J5") (pin "3") (pinfunction "GND_3") (pintype "bidirectional"))
      (node (ref "J5") (pin "5") (pinfunction "GND_5") (pintype "bidirectional"))
      (node (ref "J5") (pin "9") (pinfunction "GND_9") (pintype "bidirectional"))
      (node (ref "J6") (pin "1") (pinfunction "GND_1") (pintype "bidirectional"))
      (node (ref "J6") (pin "2") (pinfunction "GND_2") (pintype "bidirectional"))
      (node (ref "J6") (pin "32") (pinfunction "EEPROM_A2_32") (pintype "bidirectional"))
      (node (ref "J6") (pin "33") (pinfunction "GND_33") (pintype "bidirectional"))
      (node (ref "J6") (pin "34") (pinfunction "EEPROM_A1_34") (pintype "bidirectional"))
      (node (ref "J6") (pin "36") (pinfunction "EEPROM_A0_36") (pintype "bidirectional"))
      (node (ref "J6") (pin "39") (pinfunction "GND_39") (pintype "bidirectional"))
      (node (ref "J6") (pin "45") (pinfunction "GND_45") (pintype "bidirectional"))
      (node (ref "J6") (pin "75") (pinfunction "GND_75") (pintype "bidirectional"))
      (node (ref "J6") (pin "8") (pinfunction "GND_8") (pintype "bidirectional"))
      (node (ref "J7") (pin "1") (pinfunction "GND_1") (pintype "bidirectional"))
      (node (ref "J7") (pin "2") (pinfunction "GND_2") (pintype "bidirectional"))
      (node (ref "J7") (pin "32") (pinfunction "EEPROM_A2_32") (pintype "bidirectional"))
      (node (ref "J7") (pin "33") (pinfunction "GND_33") (pintype "bidirectional"))
      (node (ref "J7") (pin "34") (pinfunction "EEPROM_A1_34") (pintype "bidirectional"))
      (node (ref "J7") (pin "39") (pinfunction "GND_39") (pintype "bidirectional"))
      (node (ref "J7") (pin "45") (pinfunction "GND_45") (pintype "bidirectional"))
      (node (ref "J7") (pin "75") (pinfunction "GND_75") (pintype "bidirectional"))
      (node (ref "J7") (pin "8") (pinfunction "GND_8") (pintype "bidirectional"))
      (node (ref "J8") (pin "1") (pinfunction "-_1") (pintype "bidirectional"))
      (node (ref "J9") (pin "1") (pinfunction "1_1") (pintype "passive"))
      (node (ref "QWIIC_LED") (pin "1") (pinfunction "1_1") (pintype "passive"))
      (node (ref "R1") (pin "1") (pinfunction "1_1") (pintype "passive"))
      (node (ref "R19") (pin "2") (pinfunction "2_2") (pintype "passive"))
      (node (ref "R2") (pin "1") (pinfunction "1_1") (pintype "passive"))
      (node (ref "R3") (pin "1") (pinfunction "1_1") (pintype "passive"))
      (node (ref "R6") (pin "1") (pinfunction "1_1") (pintype "passive"))
      (node (ref "S1") (pin "1") (pinfunction "1_1") (pintype "passive"))
      (node (ref "S1") (pin "2") (pinfunction "1_2") (pintype "passive"))
      (node (ref "S2") (pin "1") (pinfunction "1_1") (pintype "passive"))
      (node (ref "S2") (pin "2") (pinfunction "1_2") (pintype "passive"))
      (node (ref "SHLD") (pin "1") (pinfunction "1_1") (pintype "passive"))
      (node (ref "U1") (pin "P5") (pinfunction "GND_P5") (pintype "power_in"))
      (node (ref "U2") (pin "2") (pinfunction "VSS_2") (pintype "power_in"))
      (node (ref "U3") (pin "2") (pinfunction "VSS_2") (pintype "bidirectional"))
      (node (ref "U4") (pin "2") (pinfunction "GND_2") (pintype "input"))
      (node (ref "U5") (pin "4") (pinfunction "GND_4") (pintype "input"))
      (node (ref "U5") (pin "EP") (pinfunction "GND_EP") (pintype "input"))
    )
    (net (code "31") (name "HOST_D+") (class "Default")
      (node (ref "J1") (pin "35") (pinfunction "USBHOST_D+_35") (pintype "bidirectional"))
      (node (ref "J6") (pin "35") (pinfunction "USBHOST_D+_35") (pintype "bidirectional"))
    )
    (net (code "32") (name "HOST_D-") (class "Default")
      (node (ref "J1") (pin "37") (pinfunction "USBHOST_D-_37") (pintype "bidirectional"))
      (node (ref "J6") (pin "37") (pinfunction "USBHOST_D-_37") (pintype "bidirectional"))
    )
    (net (code "33") (name "I2C_SCL") (class "Default")
      (node (ref "J1") (pin "14") (pinfunction "I2C_SCL_14") (pintype "bidirectional"))
      (node (ref "J2") (pin "4") (pinfunction "4_4") (pintype "passive"))
      (node (ref "J4") (pin "4") (pinfunction "4_4") (pintype "passive"))
      (node (ref "J6") (pin "21") (pinfunction "I2C_SCL_21") (pintype "bidirectional"))
      (node (ref "J7") (pin "21") (pinfunction "I2C_SCL_21") (pintype "bidirectional"))
      (node (ref "R15") (pin "1") (pinfunction "1_1") (pintype "passive"))
    )
    (net (code "34") (name "I2C_SCL1-PROCESSOR{slash}QWIIC_EN") (class "Default")
      (node (ref "J1") (pin "53") (pinfunction "I2C_SCL1_53") (pintype "bidirectional"))
      (node (ref "R4") (pin "1") (pinfunction "1_1") (pintype "passive"))
      (node (ref "U4") (pin "3") (pinfunction "EN_3") (pintype "input"))
    )
    (net (code "35") (name "I2C_SDA") (class "Default")
      (node (ref "J1") (pin "12") (pinfunction "I2C_SDA_12") (pintype "bidirectional"))
      (node (ref "J2") (pin "3") (pinfunction "3_3") (pintype "passive"))
      (node (ref "J4") (pin "3") (pinfunction "3_3") (pintype "passive"))
      (node (ref "J6") (pin "19") (pinfunction "I2C_SDA_19") (pintype "bidirectional"))
      (node (ref "J7") (pin "19") (pinfunction "I2C_SDA_19") (pintype "bidirectional"))
      (node (ref "R14") (pin "1") (pinfunction "1_1") (pintype "passive"))
    )
    (net (code "36") (name "Net-(3V3_LED-Pad2)") (class "Default")
      (node (ref "3V3_LED") (pin "2") (pinfunction "2_2") (pintype "passive"))
      (node (ref "D3") (pin "C") (pinfunction "C_C") (pintype "passive"))
    )
    (net (code "37") (name "Net-(5V_LED-Pad2)") (class "Default")
      (node (ref "5V_LED") (pin "2") (pinfunction "2_2") (pintype "passive"))
      (node (ref "D8") (pin "C") (pinfunction "C_C") (pintype "passive"))
    )
    (net (code "38") (name "Net-(D2-PadA)") (class "Default")
      (node (ref "D2") (pin "A") (pinfunction "A_A") (pintype "passive"))
      (node (ref "R16") (pin "1") (pinfunction "1_1") (pintype "passive"))
    )
    (net (code "39") (name "Net-(D2-PadC)") (class "Default")
      (node (ref "D2") (pin "C") (pinfunction "C_C") (pintype "passive"))
      (node (ref "QWIIC_LED") (pin "2") (pinfunction "2_2") (pintype "passive"))
    )
    (net (code "40") (name "Net-(D3-PadA)") (class "Default")
      (node (ref "D3") (pin "A") (pinfunction "A_A") (pintype "passive"))
      (node (ref "R11") (pin "1") (pinfunction "1_1") (pintype "passive"))
    )
    (net (code "41") (name "Net-(D4-PadA)") (class "Default")
      (node (ref "D4") (pin "A") (pinfunction "A_A") (pintype "passive"))
      (node (ref "R5") (pin "2") (pinfunction "2_2") (pintype "passive"))
    )
    (net (code "42") (name "Net-(D8-PadA)") (class "Default")
      (node (ref "D8") (pin "A") (pinfunction "A_A") (pintype "passive"))
      (node (ref "R8") (pin "1") (pinfunction "1_1") (pintype "passive"))
    )
    (net (code "43") (name "Net-(DIVIDER-Pad2)") (class "Default")
      (node (ref "DIVIDER") (pin "2") (pinfunction "2_2") (pintype "passive"))
      (node (ref "R7") (pin "1") (pinfunction "1_1") (pintype "passive"))
    )
    (net (code "44") (name "Net-(I2C_PU-Pad1)") (class "Default")
      (node (ref "I2C_PU") (pin "1") (pinfunction "1_1") (pintype "passive"))
      (node (ref "R15") (pin "2") (pinfunction "2_2") (pintype "passive"))
    )
    (net (code "45") (name "Net-(I2C_PU-Pad3)") (class "Default")
      (node (ref "I2C_PU") (pin "3") (pinfunction "3_3") (pintype "passive"))
      (node (ref "R14") (pin "2") (pinfunction "2_2") (pintype "passive"))
    )
    (net (code "46") (name "Net-(J3-CC1)") (class "Default")
      (node (ref "J3") (pin "A5") (pinfunction "CC1_A5") (pintype "bidirectional"))
      (node (ref "R1") (pin "2") (pinfunction "2_2") (pintype "passive"))
    )
    (net (code "47") (name "Net-(J3-CC2)") (class "Default")
      (node (ref "J3") (pin "B5") (pinfunction "CC2_B5") (pintype "bidirectional"))
      (node (ref "R2") (pin "2") (pinfunction "2_2") (pintype "passive"))
    )
    (net (code "48") (name "Net-(J3-SHLD-PadSHLD1)") (class "Default")
      (node (ref "J3") (pin "SHLD1") (pinfunction "SHLD_SHLD1") (pintype "bidirectional"))
      (node (ref "J3") (pin "SHLD2") (pinfunction "SHLD_SHLD2") (pintype "bidirectional"))
      (node (ref "J3") (pin "SHLD3") (pinfunction "SHLD_SHLD3") (pintype "bidirectional"))
      (node (ref "J3") (pin "SHLD4") (pinfunction "SHLD_SHLD4") (pintype "bidirectional"))
      (node (ref "SHLD") (pin "2") (pinfunction "2_2") (pintype "passive"))
    )
    (net (code "49") (name "Net-(J10-VCC)") (class "Default")
      (node (ref "C7") (pin "2") (pinfunction "2_2") (pintype "passive"))
      (node (ref "J10") (pin "4") (pinfunction "VCC_4") (pintype "bidirectional"))
      (node (ref "Q2") (pin "3") (pinfunction "D_3") (pintype "bidirectional"))
    )
    (net (code "50") (name "Net-(Q2-G)") (class "Default")
      (node (ref "Q2") (pin "1") (pinfunction "G_1") (pintype "bidirectional"))
      (node (ref "R18") (pin "2") (pinfunction "2_2") (pintype "passive"))
      (node (ref "R19") (pin "1") (pinfunction "1_1") (pintype "passive"))
    )
    (net (code "51") (name "Net-(U2-PROG)") (class "Default")
      (node (ref "R3") (pin "2") (pinfunction "2_2") (pintype "passive"))
      (node (ref "U2") (pin "5") (pinfunction "PROG_5") (pintype "input"))
    )
    (net (code "52") (name "Net-(U2-STAT)") (class "Default")
      (node (ref "D4") (pin "C") (pinfunction "C_C") (pintype "passive"))
      (node (ref "U2") (pin "1") (pinfunction "STAT_1") (pintype "output"))
    )
    (net (code "53") (name "Net-(U5-EN)") (class "Default")
      (node (ref "D1") (pin "C") (pinfunction "C_C") (pintype "passive"))
      (node (ref "R9") (pin "1") (pinfunction "1_1") (pintype "passive"))
      (node (ref "U5") (pin "5") (pinfunction "EN_5") (pintype "bidirectional"))
      (node (ref "VE") (pin "2") (pinfunction "2_2") (pintype "passive"))
    )
    (net (code "54") (name "Net-(U5-IN)") (class "Default")
      (node (ref "5V_MEAS") (pin "2") (pinfunction "2_2") (pintype "passive"))
      (node (ref "5V_MEAS") (pin "4") (pinfunction "2_4") (pintype "passive"))
      (node (ref "C5") (pin "1") (pinfunction "1_1") (pintype "passive"))
      (node (ref "C8") (pin "1") (pinfunction "1_1") (pintype "passive"))
      (node (ref "R9") (pin "2") (pinfunction "2_2") (pintype "passive"))
      (node (ref "U5") (pin "8") (pinfunction "IN_8") (pintype "input"))
    )
    (net (code "55") (name "Net-(U5-OUT)") (class "Default")
      (node (ref "3V3_MEAS") (pin "1") (pinfunction "1_1") (pintype "passive"))
      (node (ref "3V3_MEAS") (pin "3") (pinfunction "1_3") (pintype "passive"))
      (node (ref "C11") (pin "1") (pinfunction "1_1") (pintype "passive"))
      (node (ref "C6") (pin "1") (pinfunction "1_1") (pintype "passive"))
      (node (ref "U5") (pin "1") (pinfunction "OUT_1") (pintype "output"))
    )
    (net (code "56") (name "PROCESSOR_CAN-RX") (class "Default")
      (node (ref "J1") (pin "41") (pinfunction "CAN-RX_41") (pintype "bidirectional"))
      (node (ref "J6") (pin "43") (pinfunction "CAN-TX_43") (pintype "bidirectional"))
    )
    (net (code "57") (name "PROCESSOR_CAN-TX") (class "Default")
      (node (ref "J1") (pin "43") (pinfunction "CAN-TX_43") (pintype "bidirectional"))
      (node (ref "J6") (pin "41") (pinfunction "CAN-RX_41") (pintype "bidirectional"))
    )
    (net (code "58") (name "PWM0-PROCESSOR") (class "Default")
      (node (ref "J1") (pin "32") (pinfunction "PWM0_32") (pintype "bidirectional"))
      (node (ref "J6") (pin "51") (pinfunction "F2/PWM_51") (pintype "bidirectional"))
    )
    (net (code "59") (name "PWM1-PROCESSOR") (class "Default")
      (node (ref "J1") (pin "47") (pinfunction "PWM1_47") (pintype "bidirectional"))
      (node (ref "J7") (pin "51") (pinfunction "F2/PWM_51") (pintype "bidirectional"))
    )
    (net (code "60") (name "RTS1-PROCESSOR") (class "Default")
      (node (ref "J1") (pin "13") (pinfunction "RTS1_13") (pintype "bidirectional"))
      (node (ref "J6") (pin "18") (pinfunction "CTS_18") (pintype "bidirectional"))
    )
    (net (code "61") (name "RX1-DFU_TX-FC0-PLEX") (class "Default")
      (node (ref "J6") (pin "4") (pinfunction "DFU_FC_TX_4") (pintype "bidirectional"))
      (node (ref "U1") (pin "P9") (pinfunction "2S1_P9") (pintype "bidirectional"))
    )
    (net (code "62") (name "RX1-DFU_TX-FC1-PLEX") (class "Default")
      (node (ref "J7") (pin "4") (pinfunction "DFU_FC_TX_4") (pintype "bidirectional"))
      (node (ref "U1") (pin "P8") (pinfunction "2S2_P8") (pintype "bidirectional"))
    )
    (net (code "63") (name "RX1-PROCESSOR") (class "Default")
      (node (ref "J1") (pin "19") (pinfunction "RX1_19") (pintype "bidirectional"))
      (node (ref "U1") (pin "P6") (pinfunction "D2_P6") (pintype "bidirectional"))
    )
    (net (code "64") (name "RX1-PROCESSOR-PLEX") (class "Default")
      (node (ref "J6") (pin "13") (pinfunction "TX_13") (pintype "bidirectional"))
      (node (ref "U1") (pin "P7") (pinfunction "2S3_P7") (pintype "bidirectional"))
    )
    (net (code "65") (name "RX2-PROCESSOR") (class "Default")
      (node (ref "J1") (pin "20") (pinfunction "RX2_20") (pintype "bidirectional"))
      (node (ref "J7") (pin "13") (pinfunction "TX_13") (pintype "bidirectional"))
    )
    (net (code "66") (name "SDIO_DATA1{slash}PWR_EN1_ALT") (class "Default")
      (node (ref "J1") (pin "66") (pinfunction "SDIO_DATA1_66") (pintype "bidirectional"))
      (node (ref "J7") (pin "71") (pinfunction "PWR_EN_71") (pintype "bidirectional"))
      (node (ref "S7") (pin "3") (pinfunction "S_3") (pintype "passive"))
    )
    (net (code "67") (name "SDIO_DATA2{slash}PWR_EN0_ALT") (class "Default")
      (node (ref "J1") (pin "68") (pinfunction "SDIO_DATA2_68") (pintype "bidirectional"))
      (node (ref "J6") (pin "71") (pinfunction "PWR_EN_71") (pintype "bidirectional"))
      (node (ref "S3") (pin "3") (pinfunction "S_3") (pintype "passive"))
    )
    (net (code "68") (name "SPI_PROCESSOR_SCK") (class "Default")
      (node (ref "J1") (pin "57") (pinfunction "SPI_SCK_57") (pintype "bidirectional"))
      (node (ref "J10") (pin "5") (pinfunction "CLK/SCK_5") (pintype "bidirectional"))
      (node (ref "J6") (pin "3") (pinfunction "SPI_SCK_3") (pintype "bidirectional"))
      (node (ref "J7") (pin "3") (pinfunction "SPI_SCK_3") (pintype "bidirectional"))
    )
    (net (code "69") (name "SPI_PROCESSOR_SDI") (class "Default")
      (node (ref "J1") (pin "61") (pinfunction "SPI_SDI_61") (pintype "bidirectional"))
      (node (ref "J10") (pin "7") (pinfunction "DAT0/SDO_7") (pintype "bidirectional"))
      (node (ref "J6") (pin "7") (pinfunction "SPI_SDO_7") (pintype "bidirectional"))
      (node (ref "J7") (pin "7") (pinfunction "SPI_SDO_7") (pintype "bidirectional"))
    )
    (net (code "70") (name "SPI_PROCESSOR_SDO") (class "Default")
      (node (ref "J1") (pin "59") (pinfunction "SPI_SDO_59") (pintype "bidirectional"))
      (node (ref "J10") (pin "3") (pinfunction "CMD/SDI_3") (pintype "bidirectional"))
      (node (ref "J6") (pin "5") (pinfunction "SPI_SDI_5") (pintype "bidirectional"))
      (node (ref "J7") (pin "5") (pinfunction "SPI_SDI_5") (pintype "bidirectional"))
    )
    (net (code "71") (name "SPI_SCK1-PROCESSOR") (class "Default")
      (node (ref "J1") (pin "60") (pinfunction "SPI_SCK1/SDIO_CLK_60") (pintype "bidirectional"))
      (node (ref "J7") (pin "61") (pinfunction "F7_61") (pintype "bidirectional"))
    )
    (net (code "72") (name "SPI_SDO1-PROCESSOR") (class "Default")
      (node (ref "J1") (pin "62") (pinfunction "SPI_SDO1/SDIO_CMD_62") (pintype "bidirectional"))
      (node (ref "J7") (pin "59") (pinfunction "F6_59") (pintype "bidirectional"))
    )
    (net (code "73") (name "SWDCK") (class "Default")
      (node (ref "J1") (pin "21") (pinfunction "SWDCK_21") (pintype "bidirectional"))
      (node (ref "J5") (pin "4") (pinfunction "SWDCLK_4") (pintype "bidirectional"))
    )
    (net (code "74") (name "SWDIO") (class "Default")
      (node (ref "J1") (pin "23") (pinfunction "SWDIO_23") (pintype "bidirectional"))
      (node (ref "J5") (pin "2") (pinfunction "SWDIO_2") (pintype "bidirectional"))
      (node (ref "TP1") (pin "1") (pinfunction "1_1") (pintype "bidirectional"))
    )
    (net (code "75") (name "TX1-DFU_RX-FC0-PLEX") (class "Default")
      (node (ref "J6") (pin "6") (pinfunction "DFU_FC_RX_6") (pintype "bidirectional"))
      (node (ref "U1") (pin "P1") (pinfunction "1S1_P1") (pintype "bidirectional"))
    )
    (net (code "76") (name "TX1-DFU_RX-FC1-PLEX") (class "Default")
      (node (ref "J7") (pin "6") (pinfunction "DFU_FC_RX_6") (pintype "bidirectional"))
      (node (ref "U1") (pin "P2") (pinfunction "1S2_P2") (pintype "bidirectional"))
    )
    (net (code "77") (name "TX1-PROCESSOR") (class "Default")
      (node (ref "J1") (pin "17") (pinfunction "TX1_17") (pintype "bidirectional"))
      (node (ref "U1") (pin "P4") (pinfunction "D1_P4") (pintype "bidirectional"))
    )
    (net (code "78") (name "TX1-PROCESSOR-PLEX") (class "Default")
      (node (ref "J6") (pin "15") (pinfunction "RX_15") (pintype "bidirectional"))
      (node (ref "U1") (pin "P3") (pinfunction "1S3_P3") (pintype "bidirectional"))
    )
    (net (code "79") (name "TX2-PROCESSOR") (class "Default")
      (node (ref "J1") (pin "22") (pinfunction "TX2_22") (pintype "bidirectional"))
      (node (ref "J7") (pin "15") (pinfunction "RX_15") (pintype "bidirectional"))
    )
    (net (code "80") (name "VCC") (class "Default")
      (node (ref "5V_MEAS") (pin "1") (pinfunction "1_1") (pintype "passive"))
      (node (ref "5V_MEAS") (pin "3") (pinfunction "1_3") (pintype "passive"))
      (node (ref "C2") (pin "1") (pinfunction "1_1") (pintype "passive"))
      (node (ref "D5") (pin "C") (pinfunction "C_C") (pintype "passive"))
      (node (ref "J6") (pin "72") (pinfunction "VCC_72") (pintype "bidirectional"))
      (node (ref "J6") (pin "74") (pinfunction "VCC_74") (pintype "bidirectional"))
      (node (ref "J7") (pin "72") (pinfunction "VCC_72") (pintype "bidirectional"))
      (node (ref "J7") (pin "74") (pinfunction "VCC_74") (pintype "bidirectional"))
      (node (ref "Q1") (pin "2") (pinfunction "S_2") (pintype "bidirectional"))
      (node (ref "R4") (pin "2") (pinfunction "2_2") (pintype "passive"))
      (node (ref "U4") (pin "1") (pinfunction "IN_1") (pintype "input"))
    )
    (net (code "81") (name "VIN") (class "Default")
      (node (ref "BYP") (pin "2") (pinfunction "2_2") (pintype "passive"))
      (node (ref "C3") (pin "1") (pinfunction "1_1") (pintype "passive"))
      (node (ref "D5") (pin "A") (pinfunction "A_A") (pintype "passive"))
      (node (ref "F2") (pin "2") (pinfunction "2_2") (pintype "bidirectional"))
      (node (ref "J1") (pin "9") (pinfunction "USB_VIN_9") (pintype "bidirectional"))
      (node (ref "Q1") (pin "1") (pinfunction "G_1") (pintype "bidirectional"))
      (node (ref "R10") (pin "2") (pinfunction "2_2") (pintype "passive"))
      (node (ref "R5") (pin "1") (pinfunction "1_1") (pintype "passive"))
      (node (ref "R6") (pin "2") (pinfunction "2_2") (pintype "passive"))
      (node (ref "R8") (pin "2") (pinfunction "2_2") (pintype "passive"))
      (node (ref "TP4") (pin "1") (pinfunction "1_1") (pintype "bidirectional"))
      (node (ref "U2") (pin "4") (pinfunction "VIN_4") (pintype "power_in"))
    )
    (net (code "82") (name "VIN{slash}3") (class "Default")
      (node (ref "J1") (pin "49") (pinfunction "BATT_VIN/3_49") (pintype "bidirectional"))
      (node (ref "R10") (pin "1") (pinfunction "1_1") (pintype "passive"))
      (node (ref "R7") (pin "2") (pinfunction "2_2") (pintype "passive"))
    )
    (net (code "83") (name "V_BATT") (class "Default")
      (node (ref "C4") (pin "1") (pinfunction "1_1") (pintype "passive"))
      (node (ref "J11") (pin "2") (pinfunction "2_2") (pintype "passive"))
      (node (ref "J8") (pin "2") (pinfunction "+_2") (pintype "bidirectional"))
      (node (ref "Q1") (pin "3") (pinfunction "D_3") (pintype "bidirectional"))
      (node (ref "TP3") (pin "1") (pinfunction "1_1") (pintype "bidirectional"))
      (node (ref "U2") (pin "3") (pinfunction "VBAT_3") (pintype "power_in"))
    )
    (net (code "84") (name "V_USB") (class "Default")
      (node (ref "BYP") (pin "1") (pinfunction "1_1") (pintype "passive"))
      (node (ref "F2") (pin "1") (pinfunction "1_1") (pintype "bidirectional"))
      (node (ref "J3") (pin "VBUS1") (pinfunction "VBUS_VBUS1") (pintype "bidirectional"))
      (node (ref "J3") (pin "VBUS2") (pinfunction "VBUS_VBUS2") (pintype "bidirectional"))
      (node (ref "U3") (pin "5") (pinfunction "VCC_5") (pintype "bidirectional"))
    )
    (net (code "85") (name "unconnected-(J1-AUD_BCLK-Pad50)") (class "Default")
      (node (ref "J1") (pin "50") (pinfunction "AUD_BCLK_50") (pintype "bidirectional"))
    )
    (net (code "86") (name "unconnected-(J1-AUD_IN{slash}CAM_PCLK-Pad54)") (class "Default")
      (node (ref "J1") (pin "54") (pinfunction "AUD_IN/CAM_PCLK_54") (pintype "bidirectional"))
    )
    (net (code "87") (name "unconnected-(J1-AUD_LRCLK-Pad52)") (class "Default")
      (node (ref "J1") (pin "52") (pinfunction "AUD_LRCLK_52") (pintype "bidirectional"))
    )
    (net (code "88") (name "unconnected-(J1-AUD_MCLK-Pad58)") (class "Default")
      (node (ref "J1") (pin "58") (pinfunction "AUD_MCLK_58") (pintype "bidirectional"))
    )
    (net (code "89") (name "unconnected-(J1-AUD_OUT{slash}CAM_MCLK-Pad56)") (class "Default")
      (node (ref "J1") (pin "56") (pinfunction "AUD_OUT/CAM_MCLK_56") (pintype "bidirectional"))
    )
    (net (code "90") (name "unconnected-(J1-G8-Pad67)") (class "Default")
      (node (ref "J1") (pin "67") (pinfunction "G8_67") (pintype "bidirectional"))
    )
    (net (code "91") (name "unconnected-(J1-G9{slash}ADC_D-{slash}CAM_HSYNC-Pad65)") (class "Default")
      (node (ref "J1") (pin "65") (pinfunction "G9/ADC_D-/CAM_HSYNC_65") (pintype "bidirectional"))
    )
    (net (code "92") (name "unconnected-(J1-G10{slash}ADC_D+{slash}CAM_VSYNC-Pad63)") (class "Default")
      (node (ref "J1") (pin "63") (pinfunction "G10/ADC_D+/CAM_VSYNC_63") (pintype "bidirectional"))
    )
    (net (code "93") (name "unconnected-(J1-G11-Pad8)") (class "Default")
      (node (ref "J1") (pin "8") (pinfunction "G11_8") (pintype "bidirectional"))
    )
    (net (code "94") (name "unconnected-(J1-RTC_3V-Pad72)") (class "Default")
      (node (ref "J1") (pin "72") (pinfunction "RTC_3V_72") (pintype "bidirectional"))
    )
    (net (code "95") (name "unconnected-(J1-SPI_SDI1{slash}SDIO_DATA0-Pad64)") (class "Default")
      (node (ref "J1") (pin "64") (pinfunction "SPI_SDI1/SDIO_DATA0_64") (pintype "bidirectional"))
    )
    (net (code "96") (name "unconnected-(J5-SWO-Pad6)") (class "Default")
      (node (ref "J5") (pin "6") (pinfunction "SWO_6") (pintype "bidirectional"))
    )
    (net (code "97") (name "unconnected-(J6-EEPROM_WP-Pad40)") (class "Default")
      (node (ref "J6") (pin "40") (pinfunction "EEPROM_WP_40") (pintype "bidirectional"))
    )
    (net (code "98") (name "unconnected-(J6-USB_VIN-Pad70)") (class "Default")
      (node (ref "J6") (pin "70") (pinfunction "USB_VIN_70") (pintype "bidirectional"))
    )
    (net (code "99") (name "unconnected-(J7-CAN-RX-Pad41)") (class "Default")
      (node (ref "J7") (pin "41") (pinfunction "CAN-RX_41") (pintype "bidirectional"))
    )
    (net (code "100") (name "unconnected-(J7-CAN-TX-Pad43)") (class "Default")
      (node (ref "J7") (pin "43") (pinfunction "CAN-TX_43") (pintype "bidirectional"))
    )
    (net (code "101") (name "unconnected-(J7-CTS-Pad18)") (class "Default")
      (node (ref "J7") (pin "18") (pinfunction "CTS_18") (pintype "bidirectional"))
    )
    (net (code "102") (name "unconnected-(J7-EEPROM_WP-Pad40)") (class "Default")
      (node (ref "J7") (pin "40") (pinfunction "EEPROM_WP_40") (pintype "bidirectional"))
    )
    (net (code "103") (name "unconnected-(J7-RTS-Pad16)") (class "Default")
      (node (ref "J7") (pin "16") (pinfunction "RTS_16") (pintype "bidirectional"))
    )
    (net (code "104") (name "unconnected-(J7-USBHOST_D+-Pad35)") (class "Default")
      (node (ref "J7") (pin "35") (pinfunction "USBHOST_D+_35") (pintype "bidirectional"))
    )
    (net (code "105") (name "unconnected-(J7-USBHOST_D--Pad37)") (class "Default")
      (node (ref "J7") (pin "37") (pinfunction "USBHOST_D-_37") (pintype "bidirectional"))
    )
    (net (code "106") (name "unconnected-(J7-USB_VIN-Pad70)") (class "Default")
      (node (ref "J7") (pin "70") (pinfunction "USB_VIN_70") (pintype "bidirectional"))
    )
    (net (code "107") (name "unconnected-(J8-PAD1-PadNC1)") (class "Default")
      (node (ref "J8") (pin "NC1") (pinfunction "PAD1_NC1") (pintype "bidirectional"))
    )
    (net (code "108") (name "unconnected-(J8-PAD2-PadNC2)") (class "Default")
      (node (ref "J8") (pin "NC2") (pinfunction "PAD2_NC2") (pintype "bidirectional"))
    )
    (net (code "109") (name "unconnected-(J10-DAT1-Pad8)") (class "Default")
      (node (ref "J10") (pin "8") (pinfunction "DAT1_8") (pintype "bidirectional"))
    )
    (net (code "110") (name "unconnected-(J10-DAT2-Pad1)") (class "Default")
      (node (ref "J10") (pin "1") (pinfunction "DAT2_1") (pintype "bidirectional"))
    )
    (net (code "111") (name "unconnected-(J10-DET-Pad9)") (class "Default")
      (node (ref "J10") (pin "9") (pinfunction "DET_9") (pintype "bidirectional"))
    )
    (net (code "112") (name "unconnected-(U3-IO1-Pad1)") (class "Default")
      (node (ref "U3") (pin "1") (pinfunction "IO1_1") (pintype "bidirectional"))
    )
    (net (code "113") (name "unconnected-(U3-IO2-Pad3)") (class "Default")
      (node (ref "U3") (pin "3") (pinfunction "IO2_3") (pintype "bidirectional"))
    )
  )
)
